# 7805-regulator.net
KiCad netlist of a schematic drawn in EAGLE
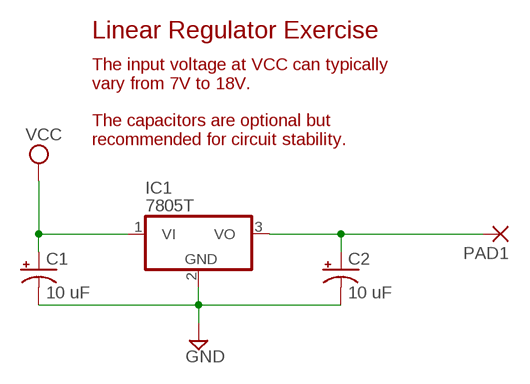
[diagram p0: schematic, sheet 1]

(export (version "E")
  (design (tool "Eeschema 10.0.6"))
  (components
    (comp (ref "C1")
      (value "10 uF")
      (footprint "eagle-import:E2,5-6")
      (libsource (lib "eagle-import") (part "CPOL-USE2.5-6"))
    )
    (comp (ref "C2")
      (value "10 uF")
      (footprint "eagle-import:E2,5-6")
      (libsource (lib "eagle-import") (part "CPOL-USE2.5-6"))
    )
    (comp (ref "IC1")
      (value "7805T")
      (footprint "eagle-import:TO220H")
      (libsource (lib "eagle-import") (part "78T05"))
    )
    (comp (ref "PAD1")
      (value "WIREPAD1,6/0,9")
      (footprint "eagle-import:1,6_0,9")
      (libsource (lib "eagle-import") (part "WIREPAD1,6/0,9"))
    )
  )
  (nets
    (net (code "1") (name "GND") (class "Default")
      (node (ref "C1") (pin "-") (pinfunction "-_-") (pintype "passive"))
      (node (ref "C2") (pin "-") (pinfunction "-_-") (pintype "passive"))
      (node (ref "IC1") (pin "2") (pinfunction "GND_2") (pintype "passive"))
    )
    (net (code "2") (name "Net-(IC1-VO)") (class "Default")
      (node (ref "C2") (pin "+") (pinfunction "+_+") (pintype "passive"))
      (node (ref "IC1") (pin "3") (pinfunction "VO_3") (pintype "passive"))
      (node (ref "PAD1") (pin "1") (pinfunction "P_1") (pintype "passive"))
    )
    (net (code "3") (name "VCC") (class "Default")
      (node (ref "C1") (pin "+") (pinfunction "+_+") (pintype "passive"))
      (node (ref "IC1") (pin "1") (pinfunction "VI_1") (pintype "input"))
    )
  )
)
